# controller_board.net
KiCad netlist of a schematic drawn in EAGLE
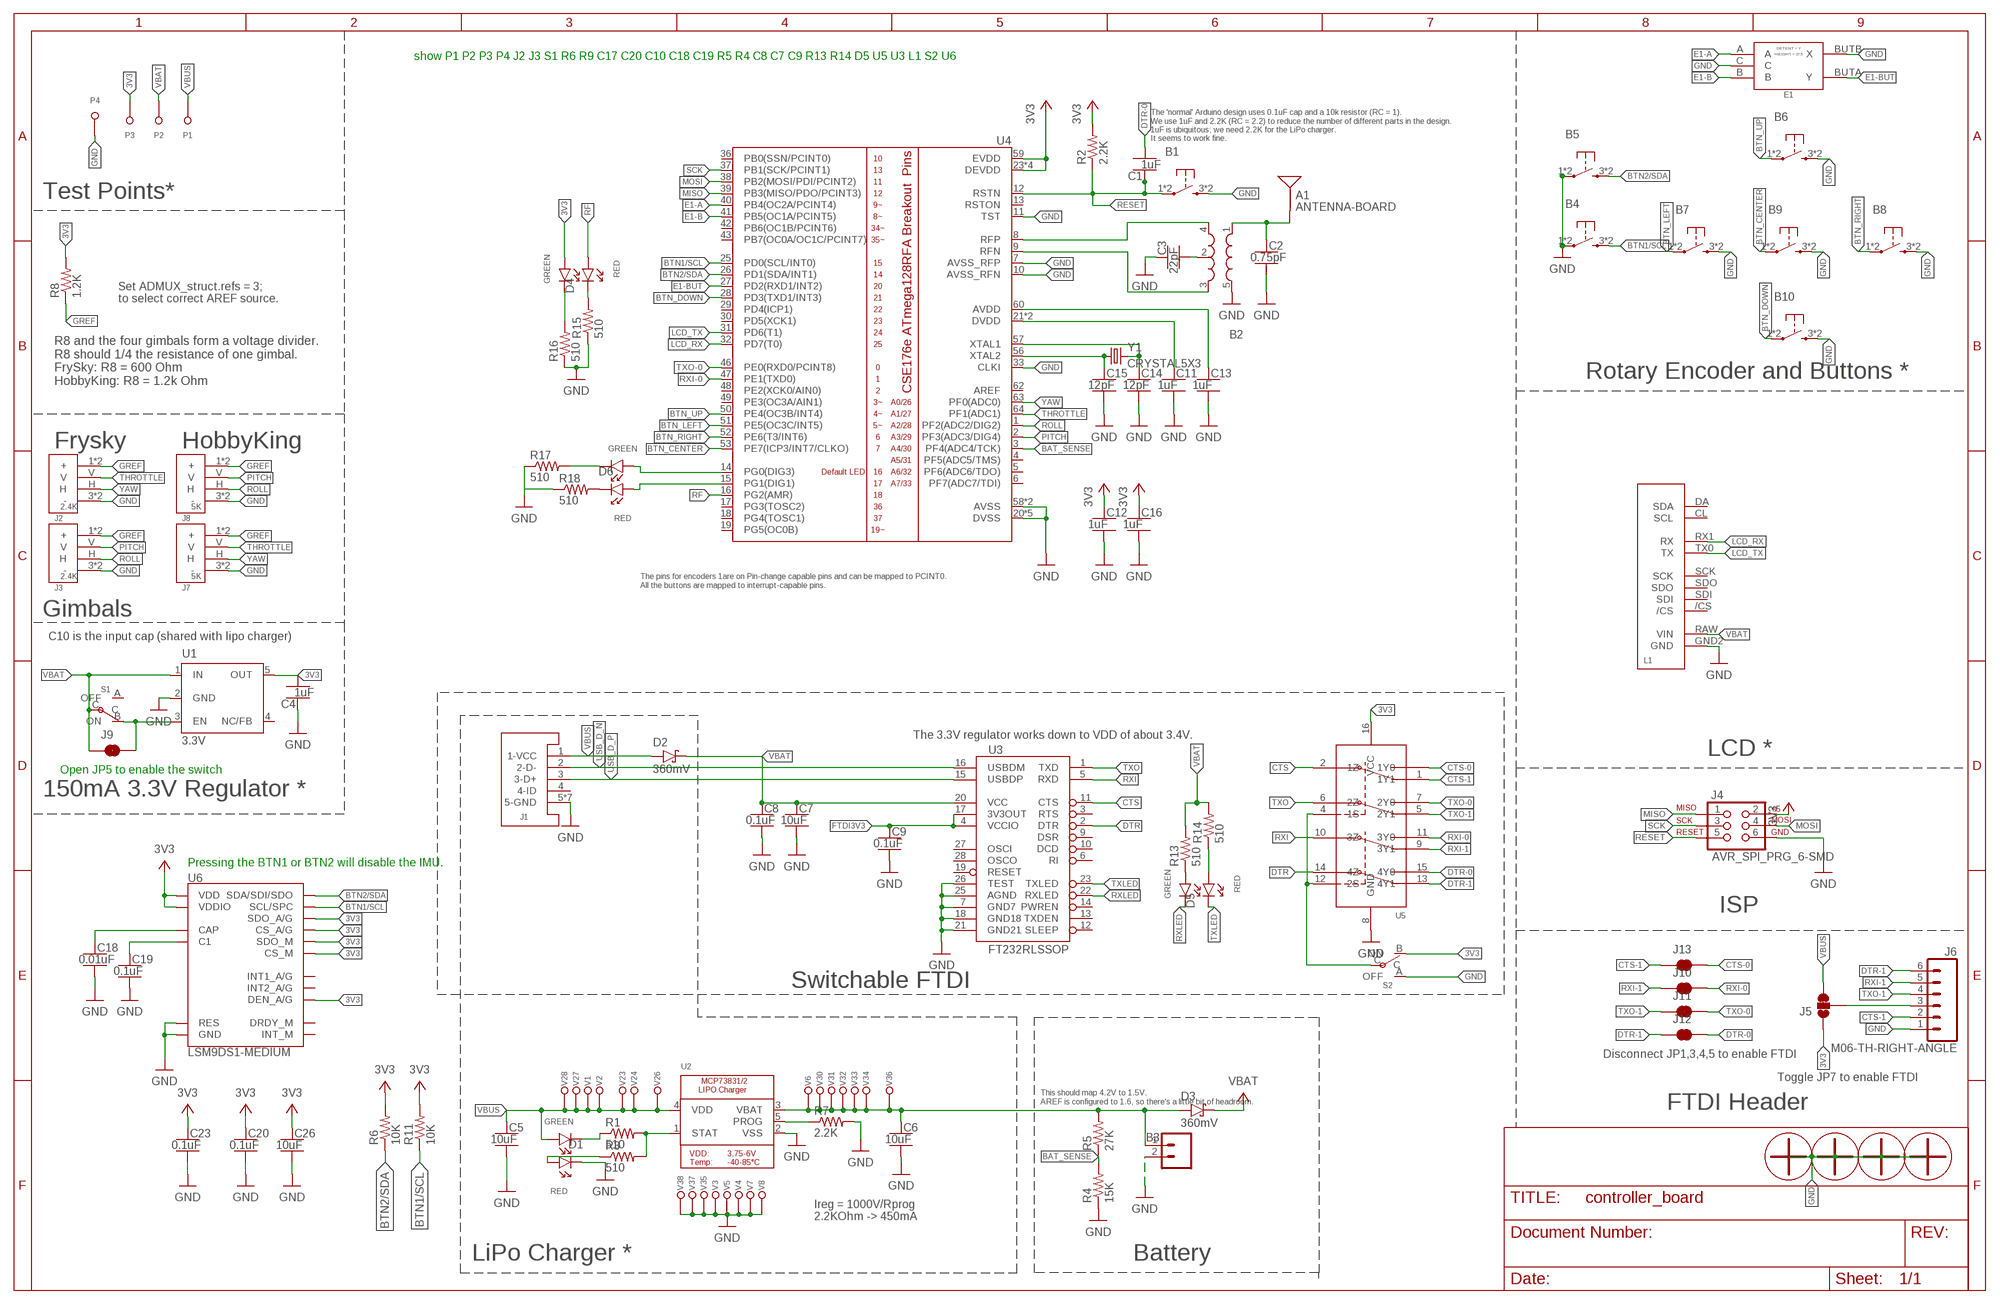
[diagram p0: schematic, sheet 1]

(export (version "E")
  (design (tool "Eeschema 10.0.6"))
  (components
    (comp (ref "A1")
      (value "ANTENNA-BOARD")
      (footprint "eagle-import:ANT_PCB_2.4GHZ_NRF8001_1.6MM_1OZ")
      (fields (field (name "CREATOR") "Swanson"))
      (libsource (lib "eagle-import") (part "ANTENNA-BOARD"))
    )
    (comp (ref "B1")
      (value "PUSHBUTTON_-4.5X4.5")
      (footprint "eagle-import:4.5MM_TACTILE_SWITCH_TL3305AF160QG")
      (fields (field (name "CREATOR") "Swanson"))
      (libsource (lib "eagle-import") (part "PUSHBUTTON_-4.5X4.5"))
    )
    (comp (ref "B2")
      (value "BALUN0805")
      (footprint "eagle-import:BALUN")
      (fields
        (field (name "MFR") "Wurth Electronics Inc")
        (field (name "MPN") "748421245")
        (field (name "CREATOR") "Swanson")
        (field (name "REVIEWER") "Swanson")
      )
      (libsource (lib "eagle-import") (part "BALUN0805"))
    )
    (comp (ref "B3")
      (value "HEADER-0.1IN-2POS-SCREW")
      (footprint "eagle-import:SCREW-TERMINAL-1X2-2.54MM")
      (fields (field (name "PIN1") "+") (field (name "PIN2") "-") (field (name "CREATOR") "Swanson"))
      (libsource (lib "eagle-import") (part "HEADER-0.1IN-2POS-SCREW"))
    )
    (comp (ref "B4")
      (value "PUSHBUTTON_-4.5X4.5")
      (footprint "eagle-import:4.5MM_TACTILE_SWITCH_TL3305AF160QG")
      (fields (field (name "CREATOR") "Swanson"))
      (libsource (lib "eagle-import") (part "PUSHBUTTON_-4.5X4.5"))
    )
    (comp (ref "B5")
      (value "PUSHBUTTON_-4.5X4.5")
      (footprint "eagle-import:4.5MM_TACTILE_SWITCH_TL3305AF160QG")
      (fields (field (name "CREATOR") "Swanson"))
      (libsource (lib "eagle-import") (part "PUSHBUTTON_-4.5X4.5"))
    )
    (comp (ref "B6")
      (value "PUSHBUTTON_-4.5X4.5")
      (footprint "eagle-import:4.5MM_TACTILE_SWITCH_TL3305AF160QG")
      (fields (field (name "CREATOR") "Swanson"))
      (libsource (lib "eagle-import") (part "PUSHBUTTON_-4.5X4.5"))
    )
    (comp (ref "B7")
      (value "PUSHBUTTON_-4.5X4.5")
      (footprint "eagle-import:4.5MM_TACTILE_SWITCH_TL3305AF160QG")
      (fields (field (name "CREATOR") "Swanson"))
      (libsource (lib "eagle-import") (part "PUSHBUTTON_-4.5X4.5"))
    )
    (comp (ref "B8")
      (value "PUSHBUTTON_-4.5X4.5")
      (footprint "eagle-import:4.5MM_TACTILE_SWITCH_TL3305AF160QG")
      (fields (field (name "CREATOR") "Swanson"))
      (libsource (lib "eagle-import") (part "PUSHBUTTON_-4.5X4.5"))
    )
    (comp (ref "B9")
      (value "PUSHBUTTON_-4.5X4.5")
      (footprint "eagle-import:4.5MM_TACTILE_SWITCH_TL3305AF160QG")
      (fields (field (name "CREATOR") "Swanson"))
      (libsource (lib "eagle-import") (part "PUSHBUTTON_-4.5X4.5"))
    )
    (comp (ref "B10")
      (value "PUSHBUTTON_-4.5X4.5")
      (footprint "eagle-import:4.5MM_TACTILE_SWITCH_TL3305AF160QG")
      (fields (field (name "CREATOR") "Swanson"))
      (libsource (lib "eagle-import") (part "PUSHBUTTON_-4.5X4.5"))
    )
    (comp (ref "C1")
      (value "1uF")
      (footprint "eagle-import:CAPC2012X140_HS")
      (fields
        (field (name "MFR") "Taiyo Yuden")
        (field (name "MPN") "TMK212B7105KG-T")
        (field (name "CREATOR") "Swanson")
        (field (name "REVIEWER") "Swanson")
      )
      (libsource (lib "eagle-import") (part "CAPACITOR-NP_SMD-2012-0805_CERAMIC-1UF"))
    )
    (comp (ref "C2")
      (value "0.75pF")
      (footprint "eagle-import:CAPC2012X140_HS")
      (fields
        (field (name "MFR") "Murata Electronics North America")
        (field (name "MPN") "GQM2195C2AR75CB01D")
        (field (name "CREATOR") "Swanson")
        (field (name "REVIEWER") "Swanson")
      )
      (libsource (lib "eagle-import") (part "CAPACITOR-NP_SMD-2012-0805_CERAMIC-0.75PF"))
    )
    (comp (ref "C3")
      (value "22pF")
      (footprint "eagle-import:CAPC2012X140_HS")
      (fields
        (field (name "MFR") "Murata Electronics North America")
        (field (name "MPN") "GRM21A5C2E220JW01D")
        (field (name "CREATOR") "Swanson")
        (field (name "REVIEWER") "Swanson")
      )
      (libsource (lib "eagle-import") (part "CAPACITOR-NP_SMD-2012-0805_CERAMIC-22PF"))
    )
    (comp (ref "C4")
      (value "1uF")
      (footprint "eagle-import:CAPC2012X140_HS")
      (fields
        (field (name "MFR") "Taiyo Yuden")
        (field (name "MPN") "TMK212B7105KG-T")
        (field (name "CREATOR") "Swanson")
        (field (name "REVIEWER") "Swanson")
      )
      (libsource (lib "eagle-import") (part "CAPACITOR-NP_SMD-2012-0805_CERAMIC-1UF"))
    )
    (comp (ref "C5")
      (value "10uF")
      (footprint "eagle-import:CAPC2012X140_HS")
      (fields (field (name "CREATOR") "Swanson") (field (name "REVIEWER") "Swanson"))
      (libsource (lib "eagle-import") (part "CAPACITOR-NP_SMD-2012-0805_CERAMIC-10UF"))
    )
    (comp (ref "C6")
      (value "10uF")
      (footprint "eagle-import:CAPC2012X140_HS")
      (fields (field (name "CREATOR") "Swanson") (field (name "REVIEWER") "Swanson"))
      (libsource (lib "eagle-import") (part "CAPACITOR-NP_SMD-2012-0805_CERAMIC-10UF"))
    )
    (comp (ref "C7")
      (value "10uF")
      (footprint "eagle-import:CAPC2012X140_HS")
      (fields (field (name "CREATOR") "Swanson") (field (name "REVIEWER") "Swanson"))
      (libsource (lib "eagle-import") (part "CAPACITOR-NP_SMD-2012-0805_CERAMIC-10UF"))
    )
    (comp (ref "C8")
      (value "0.1uF")
      (footprint "eagle-import:CAPC2012X140_HS")
      (fields
        (field (name "MFR") "TDK")
        (field (name "MPN") "C2012X7R2A104K125AA")
        (field (name "CREATOR") "Swanson")
        (field (name "REVIEWER") "Swanson")
      )
      (libsource (lib "eagle-import") (part "CAPACITOR-NP_SMD-2012-0805_CERAMIC-0.1UF"))
    )
    (comp (ref "C9")
      (value "0.1uF")
      (footprint "eagle-import:CAPC2012X140_HS")
      (fields
        (field (name "MFR") "TDK")
        (field (name "MPN") "C2012X7R2A104K125AA")
        (field (name "CREATOR") "Swanson")
        (field (name "REVIEWER") "Swanson")
      )
      (libsource (lib "eagle-import") (part "CAPACITOR-NP_SMD-2012-0805_CERAMIC-0.1UF"))
    )
    (comp (ref "C11")
      (value "1uF")
      (footprint "eagle-import:CAPC2012X140_HS")
      (fields
        (field (name "MFR") "Taiyo Yuden")
        (field (name "MPN") "TMK212B7105KG-T")
        (field (name "CREATOR") "Swanson")
        (field (name "REVIEWER") "Swanson")
      )
      (libsource (lib "eagle-import") (part "CAPACITOR-NP_SMD-2012-0805_CERAMIC-1UF"))
    )
    (comp (ref "C12")
      (value "1uF")
      (footprint "eagle-import:CAPC2012X140_HS")
      (fields
        (field (name "MFR") "Taiyo Yuden")
        (field (name "MPN") "TMK212B7105KG-T")
        (field (name "CREATOR") "Swanson")
        (field (name "REVIEWER") "Swanson")
      )
      (libsource (lib "eagle-import") (part "CAPACITOR-NP_SMD-2012-0805_CERAMIC-1UF"))
    )
    (comp (ref "C13")
      (value "1uF")
      (footprint "eagle-import:CAPC2012X140_HS")
      (fields
        (field (name "MFR") "Taiyo Yuden")
        (field (name "MPN") "TMK212B7105KG-T")
        (field (name "CREATOR") "Swanson")
        (field (name "REVIEWER") "Swanson")
      )
      (libsource (lib "eagle-import") (part "CAPACITOR-NP_SMD-2012-0805_CERAMIC-1UF"))
    )
    (comp (ref "C14")
      (value "12pF")
      (footprint "eagle-import:CAPC2012X140_HS")
      (fields
        (field (name "MFR") "Murata Electronics North America")
        (field (name "MPN") "GRM21A5C2E120JW01D")
        (field (name "CREATOR") "Swanson")
        (field (name "REVIEWER") "Swanson")
      )
      (libsource (lib "eagle-import") (part "CAPACITOR-NP_SMD-2012-0805_CERAMIC-12PF"))
    )
    (comp (ref "C15")
      (value "12pF")
      (footprint "eagle-import:CAPC2012X140_HS")
      (fields
        (field (name "MFR") "Murata Electronics North America")
        (field (name "MPN") "GRM21A5C2E120JW01D")
        (field (name "CREATOR") "Swanson")
        (field (name "REVIEWER") "Swanson")
      )
      (libsource (lib "eagle-import") (part "CAPACITOR-NP_SMD-2012-0805_CERAMIC-12PF"))
    )
    (comp (ref "C16")
      (value "1uF")
      (footprint "eagle-import:CAPC2012X140_HS")
      (fields
        (field (name "MFR") "Taiyo Yuden")
        (field (name "MPN") "TMK212B7105KG-T")
        (field (name "CREATOR") "Swanson")
        (field (name "REVIEWER") "Swanson")
      )
      (libsource (lib "eagle-import") (part "CAPACITOR-NP_SMD-2012-0805_CERAMIC-1UF"))
    )
    (comp (ref "C18")
      (value "0.01uF")
      (footprint "eagle-import:CAPC2012X140_HS")
      (fields
        (field (name "MFR") "Knowles Syfer")
        (field (name "MPN") "0805J0500104KJT")
        (field (name "CREATOR") "Swanson")
        (field (name "REVIEWER") "Swanson")
      )
      (libsource (lib "eagle-import") (part "CAPACITOR-NP_SMD-2012-0805_CERAMIC-0.01UF"))
    )
    (comp (ref "C19")
      (value "0.1uF")
      (footprint "eagle-import:CAPC2012X140_HS")
      (fields
        (field (name "MFR") "TDK")
        (field (name "MPN") "C2012X7R2A104K125AA")
        (field (name "CREATOR") "Swanson")
        (field (name "REVIEWER") "Swanson")
      )
      (libsource (lib "eagle-import") (part "CAPACITOR-NP_SMD-2012-0805_CERAMIC-0.1UF"))
    )
    (comp (ref "C20")
      (value "0.1uF")
      (footprint "eagle-import:CAPC2012X140_HS")
      (fields
        (field (name "MFR") "TDK")
        (field (name "MPN") "C2012X7R2A104K125AA")
        (field (name "CREATOR") "Swanson")
        (field (name "REVIEWER") "Swanson")
      )
      (libsource (lib "eagle-import") (part "CAPACITOR-NP_SMD-2012-0805_CERAMIC-0.1UF"))
    )
    (comp (ref "C23")
      (value "0.1uF")
      (footprint "eagle-import:CAPC2012X140_HS")
      (fields
        (field (name "MFR") "TDK")
        (field (name "MPN") "C2012X7R2A104K125AA")
        (field (name "CREATOR") "Swanson")
        (field (name "REVIEWER") "Swanson")
      )
      (libsource (lib "eagle-import") (part "CAPACITOR-NP_SMD-2012-0805_CERAMIC-0.1UF"))
    )
    (comp (ref "C26")
      (value "10uF")
      (footprint "eagle-import:CAPC2012X140_HS")
      (fields (field (name "CREATOR") "Swanson") (field (name "REVIEWER") "Swanson"))
      (libsource (lib "eagle-import") (part "CAPACITOR-NP_SMD-2012-0805_CERAMIC-10UF"))
    )
    (comp (ref "D1")
      (value "LED-2X-GREEN/RED")
      (footprint "eagle-import:LED-2X-LTST-C155")
      (fields
        (field (name "COLOR2") "RED")
        (field (name "COLOR1") "GREEN")
        (field (name "CREATOR") "Swanson")
      )
      (libsource (lib "eagle-import") (part "LED-2X-GREEN/RED"))
    )
    (comp (ref "D2")
      (value "360mV")
      (footprint "eagle-import:SOD3716X135_HS")
      (fields
        (field (name "MFR") "Toshiba Semiconductor and Storage")
        (field (name "MPN") "CRS08(TE85L,Q,M)")
        (field (name "CREATOR") "Swanson")
        (field (name "REVIEWER") "Swanson")
      )
      (libsource (lib "eagle-import") (part "DIODE-SCHOTTKY_SMD-SOD123-360MV"))
    )
    (comp (ref "D3")
      (value "360mV")
      (footprint "eagle-import:SOD3716X135_HS")
      (fields
        (field (name "MFR") "Toshiba Semiconductor and Storage")
        (field (name "MPN") "CRS08(TE85L,Q,M)")
        (field (name "CREATOR") "Swanson")
        (field (name "REVIEWER") "Swanson")
      )
      (libsource (lib "eagle-import") (part "DIODE-SCHOTTKY_SMD-SOD123-360MV"))
    )
    (comp (ref "D4")
      (value "LED-2X-GREEN/RED")
      (footprint "eagle-import:LED-2X-LTST-C155")
      (fields
        (field (name "COLOR2") "RED")
        (field (name "COLOR1") "GREEN")
        (field (name "CREATOR") "Swanson")
      )
      (libsource (lib "eagle-import") (part "LED-2X-GREEN/RED"))
    )
    (comp (ref "D5")
      (value "LED-2X-GREEN/RED")
      (footprint "eagle-import:LED-2X-LTST-C155")
      (fields
        (field (name "COLOR2") "RED")
        (field (name "COLOR1") "GREEN")
        (field (name "CREATOR") "Swanson")
      )
      (libsource (lib "eagle-import") (part "LED-2X-GREEN/RED"))
    )
    (comp (ref "D6")
      (value "LED-2X-GREEN/RED")
      (footprint "eagle-import:LED-2X-LTST-C155")
      (fields
        (field (name "COLOR2") "RED")
        (field (name "COLOR1") "GREEN")
        (field (name "CREATOR") "Swanson")
      )
      (libsource (lib "eagle-import") (part "LED-2X-GREEN/RED"))
    )
    (comp (ref "E1")
      (value "ROTARY-ENCODER-W/BUTTON-BOURNS-PEC12R-4217F")
      (footprint "eagle-import:BOURNS-PEC12R")
      (fields (field (name "DETENT") "Y") (field (name "HEIGHT") "17.5") (field (name "CREATOR") "Swanson"))
      (libsource (lib "eagle-import") (part "ROTARY-ENCODER-W/BUTTON-BOURNS-PEC12R-4217F"))
    )
    (comp (ref "H1")
      (value "MOUNTING-HOLE-2-56-GROUNDED")
      (footprint "eagle-import:2-56-MOUNTING-HOLE")
      (fields (field (name "CREATOR") "Swanson"))
      (libsource (lib "eagle-import") (part "MOUNTING-HOLE-2-56-GROUNDED"))
    )
    (comp (ref "H2")
      (value "MOUNTING-HOLE-2-56-GROUNDED")
      (footprint "eagle-import:2-56-MOUNTING-HOLE")
      (fields (field (name "CREATOR") "Swanson"))
      (libsource (lib "eagle-import") (part "MOUNTING-HOLE-2-56-GROUNDED"))
    )
    (comp (ref "H3")
      (value "MOUNTING-HOLE-2-56-GROUNDED")
      (footprint "eagle-import:2-56-MOUNTING-HOLE")
      (fields (field (name "CREATOR") "Swanson"))
      (libsource (lib "eagle-import") (part "MOUNTING-HOLE-2-56-GROUNDED"))
    )
    (comp (ref "H4")
      (value "MOUNTING-HOLE-2-56-GROUNDED")
      (footprint "eagle-import:2-56-MOUNTING-HOLE")
      (fields (field (name "CREATOR") "Swanson"))
      (libsource (lib "eagle-import") (part "MOUNTING-HOLE-2-56-GROUNDED"))
    )
    (comp (ref "J1")
      (value "USB-MICROA-AMPHENOL-10118192-0001LF")
      (footprint "eagle-import:USB-MICROA-10118192-0001LF")
      (fields (field (name "CREATOR") "Swanson"))
      (libsource (lib "eagle-import") (part "USB-MICROA-AMPHENOL-10118192-0001LF"))
    )
    (comp (ref "J2")
      (value "2.4K")
      (footprint "eagle-import:JST-13-PTH")
      (fields (field (name "CREATOR") "Swanson"))
      (libsource (lib "eagle-import") (part "FRSKY-GIMBAL-FRYSKY"))
    )
    (comp (ref "J3")
      (value "2.4K")
      (footprint "eagle-import:JST-13-PTH")
      (fields (field (name "SPICEPREFIX") "E") (field (name "CREATOR") "Swanson"))
      (libsource (lib "eagle-import") (part "FRSKY-GIMBAL-FRYSKY"))
    )
    (comp (ref "J4")
      (value "AVR_SPI_PRG_6-SMD")
      (footprint "eagle-import:2X3-SMD")
      (fields (field (name "CREATOR") "Swanson"))
      (libsource (lib "eagle-import") (part "AVR_SPI_PRG_6-SMD"))
    )
    (comp (ref "J5")
      (value "JUMPER-SMT_3_1-NC_TRACE_NO-SILK")
      (footprint "eagle-import:SMT-JUMPER_3_1-NC_TRACE_NO-SILK")
      (fields (field (name "CREATOR") "Sparkfun"))
      (libsource (lib "eagle-import") (part "JUMPER-SMT_3_1-NC_TRACE_NO-SILK"))
    )
    (comp (ref "J6")
      (value "M06-TH-RIGHT-ANGLE")
      (footprint "eagle-import:1X06-SIP-RIGHT-ANGLE")
      (fields (field (name "CREATOR") "Swanson"))
      (libsource (lib "eagle-import") (part "M06-TH-RIGHT-ANGLE"))
    )
    (comp (ref "J7")
      (value "5K")
      (footprint "eagle-import:2X-GIMBAL-SERVO")
      (fields (field (name "CREATOR") "Swanson"))
      (libsource (lib "eagle-import") (part "FRSKY-GIMBAL-2X-SERVO"))
    )
    (comp (ref "J8")
      (value "5K")
      (footprint "eagle-import:2X-GIMBAL-SERVO")
      (fields (field (name "CREATOR") "Swanson"))
      (libsource (lib "eagle-import") (part "FRSKY-GIMBAL-2X-SERVO"))
    )
    (comp (ref "J9")
      (value "JUMPER-SMT_2_NC_TRACE_NO-SILK")
      (footprint "eagle-import:SMT-JUMPER_2_NC_TRACE_NO-SILK")
      (fields (field (name "CREATOR") "Sparkfun"))
      (libsource (lib "eagle-import") (part "JUMPER-SMT_2_NC_TRACE_NO-SILK"))
    )
    (comp (ref "J10")
      (value "JUMPER-SMT_2_NC_TRACE_NO-SILK")
      (footprint "eagle-import:SMT-JUMPER_2_NC_TRACE_NO-SILK")
      (fields (field (name "CREATOR") "Sparkfun"))
      (libsource (lib "eagle-import") (part "JUMPER-SMT_2_NC_TRACE_NO-SILK"))
    )
    (comp (ref "J11")
      (value "JUMPER-SMT_2_NC_TRACE_NO-SILK")
      (footprint "eagle-import:SMT-JUMPER_2_NC_TRACE_NO-SILK")
      (fields (field (name "CREATOR") "Sparkfun"))
      (libsource (lib "eagle-import") (part "JUMPER-SMT_2_NC_TRACE_NO-SILK"))
    )
    (comp (ref "J12")
      (value "JUMPER-SMT_2_NC_TRACE_NO-SILK")
      (footprint "eagle-import:SMT-JUMPER_2_NC_TRACE_NO-SILK")
      (fields (field (name "CREATOR") "Sparkfun"))
      (libsource (lib "eagle-import") (part "JUMPER-SMT_2_NC_TRACE_NO-SILK"))
    )
    (comp (ref "J13")
      (value "JUMPER-SMT_2_NC_TRACE_NO-SILK")
      (footprint "eagle-import:SMT-JUMPER_2_NC_TRACE_NO-SILK")
      (fields (field (name "CREATOR") "Sparkfun"))
      (libsource (lib "eagle-import") (part "JUMPER-SMT_2_NC_TRACE_NO-SILK"))
    )
    (comp (ref "L1")
      (value "SPARKFUN_SERLCD_SERIAL_REDUCED")
      (footprint "eagle-import:SPARKFUN_SERLCD_16X2_REDUCED")
      (fields (field (name "CREATOR") "Swanson"))
      (libsource (lib "eagle-import") (part "SPARKFUN_SERLCD_SERIAL_REDUCED"))
    )
    (comp (ref "P1")
      (value "TEST-POINT")
      (footprint "eagle-import:TEST-POINT-KEYSTONE-5000")
      (fields (field (name "CREATOR") "Swanson"))
      (libsource (lib "eagle-import") (part "TEST-POINT"))
    )
    (comp (ref "P2")
      (value "TEST-POINT")
      (footprint "eagle-import:TEST-POINT-KEYSTONE-5000")
      (fields (field (name "CREATOR") "Swanson"))
      (libsource (lib "eagle-import") (part "TEST-POINT"))
    )
    (comp (ref "P3")
      (value "TEST-POINT")
      (footprint "eagle-import:TEST-POINT-KEYSTONE-5000")
      (fields (field (name "CREATOR") "Swanson"))
      (libsource (lib "eagle-import") (part "TEST-POINT"))
    )
    (comp (ref "P4")
      (value "TEST-POINT")
      (footprint "eagle-import:TEST-POINT-KEYSTONE-5000")
      (fields (field (name "CREATOR") "Swanson"))
      (libsource (lib "eagle-import") (part "TEST-POINT"))
    )
    (comp (ref "R1")
      (value "510")
      (footprint "eagle-import:RESC2012X60_HS")
      (fields (field (name "CREATOR") "SWANSON"))
      (libsource (lib "eagle-import") (part "RESISTOR_SMD-2012-0805-510"))
    )
    (comp (ref "R2")
      (value "2.2K")
      (footprint "eagle-import:RESC2012X60_HS")
      (fields (field (name "CREATOR") "SWANSON"))
      (libsource (lib "eagle-import") (part "RESISTOR_SMD-2012-0805-2.2K"))
    )
    (comp (ref "R3")
      (value "510")
      (footprint "eagle-import:RESC2012X60_HS")
      (fields (field (name "CREATOR") "SWANSON"))
      (libsource (lib "eagle-import") (part "RESISTOR_SMD-2012-0805-510"))
    )
    (comp (ref "R4")
      (value "15K")
      (footprint "eagle-import:RESC2012X60_HS")
      (fields (field (name "CREATOR") "SWANSON"))
      (libsource (lib "eagle-import") (part "RESISTOR_SMD-2012-0805-15K"))
    )
    (comp (ref "R5")
      (value "27K")
      (footprint "eagle-import:RESC2012X60_HS")
      (fields (field (name "CREATOR") "Swanson"))
      (libsource (lib "eagle-import") (part "RESISTOR_SMD-2012-0805-27K"))
    )
    (comp (ref "R6")
      (value "10K")
      (footprint "eagle-import:RESC2012X60_HS")
      (fields
        (field (name "MFR") "Yageo")
        (field (name "MPN") "RC0805JR-0710KL")
        (field (name "CREATOR") "Swanson")
        (field (name "REVIEWER") "Swanson")
      )
      (libsource (lib "eagle-import") (part "RESISTOR_SMD-2012-0805-10K"))
    )
    (comp (ref "R7")
      (value "2.2K")
      (footprint "eagle-import:RESC2012X60_HS")
      (fields (field (name "CREATOR") "SWANSON"))
      (libsource (lib "eagle-import") (part "RESISTOR_SMD-2012-0805-2.2K"))
    )
    (comp (ref "R8")
      (value "1.2K")
      (footprint "eagle-import:RESC2012X60_HS")
      (fields (field (name "CREATOR") "Swanson"))
      (libsource (lib "eagle-import") (part "RESISTOR_SMD-2012-0805-1.2K"))
    )
    (comp (ref "R11")
      (value "10K")
      (footprint "eagle-import:RESC2012X60_HS")
      (fields
        (field (name "MFR") "Yageo")
        (field (name "MPN") "RC0805JR-0710KL")
        (field (name "CREATOR") "Swanson")
        (field (name "REVIEWER") "Swanson")
      )
      (libsource (lib "eagle-import") (part "RESISTOR_SMD-2012-0805-10K"))
    )
    (comp (ref "R13")
      (value "510")
      (footprint "eagle-import:RESC2012X60_HS")
      (fields (field (name "CREATOR") "SWANSON"))
      (libsource (lib "eagle-import") (part "RESISTOR_SMD-2012-0805-510"))
    )
    (comp (ref "R14")
      (value "510")
      (footprint "eagle-import:RESC2012X60_HS")
      (fields (field (name "CREATOR") "SWANSON"))
      (libsource (lib "eagle-import") (part "RESISTOR_SMD-2012-0805-510"))
    )
    (comp (ref "R15")
      (value "510")
      (footprint "eagle-import:RESC2012X60_HS")
      (fields (field (name "CREATOR") "SWANSON"))
      (libsource (lib "eagle-import") (part "RESISTOR_SMD-2012-0805-510"))
    )
    (comp (ref "R16")
      (value "510")
      (footprint "eagle-import:RESC2012X60_HS")
      (fields (field (name "CREATOR") "SWANSON"))
      (libsource (lib "eagle-import") (part "RESISTOR_SMD-2012-0805-510"))
    )
    (comp (ref "R17")
      (value "510")
      (footprint "eagle-import:RESC2012X60_HS")
      (fields (field (name "CREATOR") "SWANSON"))
      (libsource (lib "eagle-import") (part "RESISTOR_SMD-2012-0805-510"))
    )
    (comp (ref "R18")
      (value "510")
      (footprint "eagle-import:RESC2012X60_HS")
      (fields (field (name "CREATOR") "SWANSON"))
      (libsource (lib "eagle-import") (part "RESISTOR_SMD-2012-0805-510"))
    )
    (comp (ref "S1")
      (value "POWER-SWITCH-MFS201N-9-ZJS102011SAQN")
      (footprint "eagle-import:JS102011SAQN")
      (fields (field (name "CREATOR") "Swanson"))
      (libsource (lib "eagle-import") (part "POWER-SWITCH-MFS201N-9-ZJS102011SAQN"))
    )
    (comp (ref "S2")
      (value "POWER-SWITCH-MFS201N-9-ZJS102011SAQN")
      (footprint "eagle-import:JS102011SAQN")
      (fields (field (name "CREATOR") "Swanson"))
      (libsource (lib "eagle-import") (part "POWER-SWITCH-MFS201N-9-ZJS102011SAQN"))
    )
    (comp (ref "U1")
      (value "3.3V")
      (footprint "eagle-import:SOT23-DBV")
      (fields (field (name "CREATOR") "Swanson"))
      (libsource (lib "eagle-import") (part "TPS73633-DBVT3V3"))
    )
    (comp (ref "U2")
      (value "MCP73831T-2ACI/OT")
      (footprint "eagle-import:SOT23-5")
      (fields (field (name "CREATOR") "Adafruit"))
      (libsource (lib "eagle-import") (part "MCP73831/2"))
    )
    (comp (ref "U3")
      (value "FT232RLSSOP")
      (footprint "eagle-import:SSOP28DB")
      (fields (field (name "CREATOR") "Swanson"))
      (libsource (lib "eagle-import") (part "FT232RLSSOP"))
    )
    (comp (ref "U4")
      (value "ATMEGA128RFA1")
      (footprint "eagle-import:QFN-64")
      (fields
        (field (name "MFR") "Atmel")
        (field (name "MPN") "ATMEGA128RFA1-ZUR00")
        (field (name "CREATOR") "Swanson")
        (field (name "REVIEWER") "Swanson")
      )
      (libsource (lib "eagle-import") (part "ATMEGA128RFA1"))
    )
    (comp (ref "U5")
      (value "DPDT-X2")
      (footprint "eagle-import:SOP65P640X110-16")
      (fields (field (name "CREATOR") "Swanson"))
      (libsource (lib "eagle-import") (part "DPDT-X2"))
    )
    (comp (ref "U6")
      (value "LSM9DS1-MEDIUM")
      (footprint "eagle-import:NEW_IMU_MEDIUM")
      (fields (field (name "CREATOR") "PBROWN"))
      (libsource (lib "eagle-import") (part "LSM9DS1-MEDIUM"))
    )
    (comp (ref "V1")
      (value "LOCKED-VIA-0.2")
      (footprint "eagle-import:VIA-0.2MM")
      (fields (field (name "CREATOR") "Swanson"))
      (libsource (lib "eagle-import") (part "LOCKED-VIA-0.2"))
    )
    (comp (ref "V2")
      (value "LOCKED-VIA-0.2")
      (footprint "eagle-import:VIA-0.2MM")
      (fields (field (name "CREATOR") "Swanson"))
      (libsource (lib "eagle-import") (part "LOCKED-VIA-0.2"))
    )
    (comp (ref "V3")
      (value "LOCKED-VIA-0.2")
      (footprint "eagle-import:VIA-0.2MM")
      (fields (field (name "CREATOR") "Swanson"))
      (libsource (lib "eagle-import") (part "LOCKED-VIA-0.2"))
    )
    (comp (ref "V4")
      (value "LOCKED-VIA-0.2")
      (footprint "eagle-import:VIA-0.2MM")
      (fields (field (name "CREATOR") "Swanson"))
      (libsource (lib "eagle-import") (part "LOCKED-VIA-0.2"))
    )
    (comp (ref "V5")
      (value "LOCKED-VIA-0.2")
      (footprint "eagle-import:VIA-0.2MM")
      (fields (field (name "CREATOR") "Swanson"))
      (libsource (lib "eagle-import") (part "LOCKED-VIA-0.2"))
    )
    (comp (ref "V6")
      (value "LOCKED-VIA-0.2")
      (footprint "eagle-import:VIA-0.2MM")
      (fields (field (name "CREATOR") "Swanson"))
      (libsource (lib "eagle-import") (part "LOCKED-VIA-0.2"))
    )
    (comp (ref "V7")
      (value "LOCKED-VIA-0.2")
      (footprint "eagle-import:VIA-0.2MM")
      (fields (field (name "CREATOR") "Swanson"))
      (libsource (lib "eagle-import") (part "LOCKED-VIA-0.2"))
    )
    (comp (ref "V8")
      (value "LOCKED-VIA-0.2")
      (footprint "eagle-import:VIA-0.2MM")
      (fields (field (name "CREATOR") "Swanson"))
      (libsource (lib "eagle-import") (part "LOCKED-VIA-0.2"))
    )
    (comp (ref "V23")
      (value "LOCKED-VIA-0.2")
      (footprint "eagle-import:VIA-0.2MM")
      (fields (field (name "CREATOR") "Swanson"))
      (libsource (lib "eagle-import") (part "LOCKED-VIA-0.2"))
    )
    (comp (ref "V24")
      (value "LOCKED-VIA-0.2")
      (footprint "eagle-import:VIA-0.2MM")
      (fields (field (name "CREATOR") "Swanson"))
      (libsource (lib "eagle-import") (part "LOCKED-VIA-0.2"))
    )
    (comp (ref "V26")
      (value "LOCKED-VIA-0.2")
      (footprint "eagle-import:VIA-0.2MM")
      (fields (field (name "CREATOR") "Swanson"))
      (libsource (lib "eagle-import") (part "LOCKED-VIA-0.2"))
    )
    (comp (ref "V27")
      (value "LOCKED-VIA-0.2")
      (footprint "eagle-import:VIA-0.2MM")
      (fields (field (name "CREATOR") "Swanson"))
      (libsource (lib "eagle-import") (part "LOCKED-VIA-0.2"))
    )
    (comp (ref "V28")
      (value "LOCKED-VIA-0.2")
      (footprint "eagle-import:VIA-0.2MM")
      (fields (field (name "CREATOR") "Swanson"))
      (libsource (lib "eagle-import") (part "LOCKED-VIA-0.2"))
    )
    (comp (ref "V30")
      (value "LOCKED-VIA-0.2")
      (footprint "eagle-import:VIA-0.2MM")
      (fields (field (name "CREATOR") "Swanson"))
      (libsource (lib "eagle-import") (part "LOCKED-VIA-0.2"))
    )
    (comp (ref "V31")
      (value "LOCKED-VIA-0.2")
      (footprint "eagle-import:VIA-0.2MM")
      (fields (field (name "CREATOR") "Swanson"))
      (libsource (lib "eagle-import") (part "LOCKED-VIA-0.2"))
    )
    (comp (ref "V32")
      (value "LOCKED-VIA-0.2")
      (footprint "eagle-import:VIA-0.2MM")
      (fields (field (name "CREATOR") "Swanson"))
      (libsource (lib "eagle-import") (part "LOCKED-VIA-0.2"))
    )
    (comp (ref "V33")
      (value "LOCKED-VIA-0.2")
      (footprint "eagle-import:VIA-0.2MM")
      (fields (field (name "CREATOR") "Swanson"))
      (libsource (lib "eagle-import") (part "LOCKED-VIA-0.2"))
    )
    (comp (ref "V34")
      (value "LOCKED-VIA-0.2")
      (footprint "eagle-import:VIA-0.2MM")
      (fields (field (name "CREATOR") "Swanson"))
      (libsource (lib "eagle-import") (part "LOCKED-VIA-0.2"))
    )
    (comp (ref "V35")
      (value "LOCKED-VIA-0.2")
      (footprint "eagle-import:VIA-0.2MM")
      (fields (field (name "CREATOR") "Swanson"))
      (libsource (lib "eagle-import") (part "LOCKED-VIA-0.2"))
    )
    (comp (ref "V36")
      (value "LOCKED-VIA-0.2")
      (footprint "eagle-import:VIA-0.2MM")
      (fields (field (name "CREATOR") "Swanson"))
      (libsource (lib "eagle-import") (part "LOCKED-VIA-0.2"))
    )
    (comp (ref "V37")
      (value "LOCKED-VIA-0.2")
      (footprint "eagle-import:VIA-0.2MM")
      (fields (field (name "CREATOR") "Swanson"))
      (libsource (lib "eagle-import") (part "LOCKED-VIA-0.2"))
    )
    (comp (ref "V38")
      (value "LOCKED-VIA-0.2")
      (footprint "eagle-import:VIA-0.2MM")
      (fields (field (name "CREATOR") "Swanson"))
      (libsource (lib "eagle-import") (part "LOCKED-VIA-0.2"))
    )
    (comp (ref "Y1")
      (value "CRYSTAL5X3")
      (footprint "eagle-import:CRYSTAL-SMD-5X3")
      (fields
        (field (name "MFR") "Abracon LLC")
        (field (name "MPN") "ABM3B-16.000MHZ-B2-T")
        (field (name "CREATOR") "Swanson")
        (field (name "REVIEWER") "Swanson")
      )
      (libsource (lib "eagle-import") (part "CRYSTAL5X3"))
    )
  )
  (nets
    (net (code "1") (name "3V3") (class "Default")
      (node (ref "C12") (pin "1") (pinfunction "1_1") (pintype "passive"))
      (node (ref "C16") (pin "1") (pinfunction "1_1") (pintype "passive"))
      (node (ref "C20") (pin "1") (pinfunction "1_1") (pintype "passive"))
      (node (ref "C23") (pin "1") (pinfunction "1_1") (pintype "passive"))
      (node (ref "C26") (pin "1") (pinfunction "1_1") (pintype "passive"))
      (node (ref "C4") (pin "2") (pinfunction "2_2") (pintype "passive"))
      (node (ref "D4") (pin "A2") (pinfunction "A2_A2") (pintype "passive"))
      (node (ref "J4") (pin "2") (pinfunction "2_2") (pintype "passive"))
      (node (ref "J5") (pin "1") (pinfunction "1_1") (pintype "passive"))
      (node (ref "P3") (pin "T") (pinfunction "T_T") (pintype "bidirectional"))
      (node (ref "R11") (pin "2") (pinfunction "2_2") (pintype "passive"))
      (node (ref "R2") (pin "2") (pinfunction "2_2") (pintype "passive"))
      (node (ref "R6") (pin "2") (pinfunction "2_2") (pintype "passive"))
      (node (ref "R8") (pin "2") (pinfunction "2_2") (pintype "passive"))
      (node (ref "S2") (pin "B") (pinfunction "ON_B") (pintype "bidirectional"))
      (node (ref "U1") (pin "5") (pinfunction "OUT_5") (pintype "passive"))
      (node (ref "U4") (pin "23") (pinfunction "DEVDD_23") (pintype "bidirectional"))
      (node (ref "U4") (pin "34") (pinfunction "DEVDD_34") (pintype "bidirectional"))
      (node (ref "U4") (pin "44") (pinfunction "DEVDD_44") (pintype "bidirectional"))
      (node (ref "U4") (pin "54") (pinfunction "DEVDD_54") (pintype "bidirectional"))
      (node (ref "U4") (pin "59") (pinfunction "EVDD_59") (pintype "bidirectional"))
      (node (ref "U5") (pin "16") (pinfunction "VCC_16") (pintype "bidirectional"))
      (node (ref "U6") (pin "CS_A/G") (pinfunction "CS_A/G_CS_A/G") (pintype "bidirectional"))
      (node (ref "U6") (pin "CS_M") (pinfunction "CS_M_CS_M") (pintype "bidirectional"))
      (node (ref "U6") (pin "DEN_A/G") (pinfunction "DEN_A/G_DEN_A/G") (pintype "bidirectional"))
      (node (ref "U6") (pin "SDO_A/G") (pinfunction "SDO_A/G_SDO_A/G") (pintype "bidirectional"))
      (node (ref "U6") (pin "SDO_M") (pinfunction "SDO_M_SDO_M") (pintype "bidirectional"))
      (node (ref "U6") (pin "VDD1") (pinfunction "VDD_VDD1") (pintype "bidirectional"))
      (node (ref "U6") (pin "VDD2") (pinfunction "VDD_VDD2") (pintype "bidirectional"))
      (node (ref "U6") (pin "VDDIO") (pinfunction "VDDIO_VDDIO") (pintype "bidirectional"))
      (node (ref "U6") (pin "VDDIO2") (pinfunction "VDDIO_VDDIO2") (pintype "bidirectional"))
    )
    (net (code "2") (name "BAT_SENSE") (class "Default")
      (node (ref "R4") (pin "2") (pinfunction "2_2") (pintype "passive"))
      (node (ref "R5") (pin "1") (pinfunction "1_1") (pintype "passive"))
      (node (ref "U4") (pin "3") (pinfunction "PF4(ADC4/TCK)_3") (pintype "bidirectional"))
    )
    (net (code "3") (name "BTN1{slash}SCL") (class "Default")
      (node (ref "B4") (pin "3") (pinfunction "2_3") (pintype "passive"))
      (node (ref "B4") (pin "4") (pinfunction "2_4") (pintype "passive"))
      (node (ref "R11") (pin "1") (pinfunction "1_1") (pintype "passive"))
      (node (ref "U4") (pin "25") (pinfunction "PD0(SCL/INT0)_25") (pintype "bidirectional"))
      (node (ref "U6") (pin "SCL/SPC") (pinfunction "SCL/SPC_SCL/SPC") (pintype "bidirectional"))
    )
    (net (code "4") (name "BTN2{slash}SDA") (class "Default")
      (node (ref "B5") (pin "3") (pinfunction "2_3") (pintype "passive"))
      (node (ref "B5") (pin "4") (pinfunction "2_4") (pintype "passive"))
      (node (ref "R6") (pin "1") (pinfunction "1_1") (pintype "passive"))
      (node (ref "U4") (pin "26") (pinfunction "PD1(SDA/INT1)_26") (pintype "bidirectional"))
      (node (ref "U6") (pin "SDA/SDI/SDO") (pinfunction "SDA/SDI/SDO_SDA/SDI/SDO") (pintype "bidirectional"))
    )
    (net (code "5") (name "BTN_CENTER") (class "Default")
      (node (ref "B9") (pin "1") (pinfunction "1_1") (pintype "passive"))
      (node (ref "B9") (pin "2") (pinfunction "1_2") (pintype "passive"))
      (node (ref "U4") (pin "53") (pinfunction "PE7(ICP3/INT7/CLKO)_53") (pintype "bidirectional"))
    )
    (net (code "6") (name "BTN_DOWN") (class "Default")
      (node (ref "B10") (pin "1") (pinfunction "1_1") (pintype "passive"))
      (node (ref "B10") (pin "2") (pinfunction "1_2") (pintype "passive"))
      (node (ref "U4") (pin "28") (pinfunction "PD3(TXD1/INT3)_28") (pintype "bidirectional"))
    )
    (net (code "7") (name "BTN_LEFT") (class "Default")
      (node (ref "B7") (pin "1") (pinfunction "1_1") (pintype "passive"))
      (node (ref "B7") (pin "2") (pinfunction "1_2") (pintype "passive"))
      (node (ref "U4") (pin "51") (pinfunction "PE5(OC3C/INT5)_51") (pintype "bidirectional"))
    )
    (net (code "8") (name "BTN_RIGHT") (class "Default")
      (node (ref "B8") (pin "1") (pinfunction "1_1") (pintype "passive"))
      (node (ref "B8") (pin "2") (pinfunction "1_2") (pintype "passive"))
      (node (ref "U4") (pin "52") (pinfunction "PE6(T3/INT6)_52") (pintype "bidirectional"))
    )
    (net (code "9") (name "BTN_UP") (class "Default")
      (node (ref "B6") (pin "1") (pinfunction "1_1") (pintype "passive"))
      (node (ref "B6") (pin "2") (pinfunction "1_2") (pintype "passive"))
      (node (ref "U4") (pin "50") (pinfunction "PE4(OC3B/INT4)_50") (pintype "bidirectional"))
    )
    (net (code "10") (name "CTS") (class "Default")
      (node (ref "U3") (pin "11") (pinfunction "CTS_11") (pintype "input"))
      (node (ref "U5") (pin "2") (pinfunction "1Z_2") (pintype "bidirectional"))
    )
    (net (code "11") (name "CTS-0") (class "Default")
      (node (ref "J13") (pin "2") (pinfunction "2_2") (pintype "passive"))
      (node (ref "U5") (pin "3") (pinfunction "1Y0_3") (pintype "bidirectional"))
    )
    (net (code "12") (name "CTS-1") (class "Default")
      (node (ref "J13") (pin "1") (pinfunction "1_1") (pintype "passive"))
      (node (ref "J6") (pin "2") (pinfunction "2_2") (pintype "passive"))
      (node (ref "U5") (pin "1") (pinfunction "1Y1_1") (pintype "bidirectional"))
    )
    (net (code "13") (name "DTR") (class "Default")
      (node (ref "U3") (pin "2") (pinfunction "DTR_2") (pintype "output"))
      (node (ref "U5") (pin "14") (pinfunction "4Z_14") (pintype "bidirectional"))
    )
    (net (code "14") (name "DTR-0") (class "Default")
      (node (ref "C1") (pin "2") (pinfunction "2_2") (pintype "passive"))
      (node (ref "J12") (pin "2") (pinfunction "2_2") (pintype "passive"))
      (node (ref "U5") (pin "15") (pinfunction "4Y0_15") (pintype "bidirectional"))
    )
    (net (code "15") (name "DTR-1") (class "Default")
      (node (ref "J12") (pin "1") (pinfunction "1_1") (pintype "passive"))
      (node (ref "J6") (pin "6") (pinfunction "6_6") (pintype "passive"))
      (node (ref "U5") (pin "13") (pinfunction "4Y1_13") (pintype "bidirectional"))
    )
    (net (code "16") (name "E1-A") (class "Default")
      (node (ref "E1") (pin "A") (pinfunction "A_A") (pintype "bidirectional"))
      (node (ref "U4") (pin "40") (pinfunction "PB4(OC2A/PCINT4)_40") (pintype "bidirectional"))
    )
    (net (code "17") (name "E1-B") (class "Default")
      (node (ref "E1") (pin "B") (pinfunction "B_B") (pintype "bidirectional"))
      (node (ref "U4") (pin "41") (pinfunction "PB5(OC1A/PCINT5)_41") (pintype "bidirectional"))
    )
    (net (code "18") (name "E1-BUT") (class "Default")
      (node (ref "E1") (pin "BUTA") (pinfunction "Y_BUTA") (pintype "bidirectional"))
      (node (ref "U4") (pin "27") (pinfunction "PD2(RXD1/INT2)_27") (pintype "bidirectional"))
    )
    (net (code "19") (name "FTDI3V3") (class "Default")
      (node (ref "C9") (pin "1") (pinfunction "1_1") (pintype "passive"))
      (node (ref "U3") (pin "17") (pinfunction "3V3OUT_17") (pintype "output"))
      (node (ref "U3") (pin "4") (pinfunction "VCCIO_4") (pintype "power_in"))
    )
    (net (code "20") (name "GND") (class "Default")
      (node (ref "B1") (pin "3") (pinfunction "2_3") (pintype "passive"))
      (node (ref "B1") (pin "4") (pinfunction "2_4") (pintype "passive"))
      (node (ref "B10") (pin "3") (pinfunction "2_3") (pintype "passive"))
      (node (ref "B10") (pin "4") (pinfunction "2_4") (pintype "passive"))
      (node (ref "B2") (pin "5") (pinfunction "GND_5") (pintype "bidirectional"))
      (node (ref "B3") (pin "2") (pinfunction "2_2") (pintype "passive"))
      (node (ref "B4") (pin "1") (pinfunction "1_1") (pintype "passive"))
      (node (ref "B4") (pin "2") (pinfunction "1_2") (pintype "passive"))
      (node (ref "B5") (pin "1") (pinfunction "1_1") (pintype "passive"))
      (node (ref "B5") (pin "2") (pinfunction "1_2") (pintype "passive"))
      (node (ref "B6") (pin "3") (pinfunction "2_3") (pintype "passive"))
      (node (ref "B6") (pin "4") (pinfunction "2_4") (pintype "passive"))
      (node (ref "B7") (pin "3") (pinfunction "2_3") (pintype "passive"))
      (node (ref "B7") (pin "4") (pinfunction "2_4") (pintype "passive"))
      (node (ref "B8") (pin "3") (pinfunction "2_3") (pintype "passive"))
      (node (ref "B8") (pin "4") (pinfunction "2_4") (pintype "passive"))
      (node (ref "B9") (pin "3") (pinfunction "2_3") (pintype "passive"))
      (node (ref "B9") (pin "4") (pinfunction "2_4") (pintype "passive"))
      (node (ref "C11") (pin "2") (pinfunction "2_2") (pintype "passive"))
      (node (ref "C12") (pin "2") (pinfunction "2_2") (pintype "passive"))
      (node (ref "C13") (pin "2") (pinfunction "2_2") (pintype "passive"))
      (node (ref "C14") (pin "2") (pinfunction "2_2") (pintype "passive"))
      (node (ref "C15") (pin "2") (pinfunction "2_2") (pintype "passive"))
      (node (ref "C16") (pin "2") (pinfunction "2_2") (pintype "passive"))
      (node (ref "C18") (pin "2") (pinfunction "2_2") (pintype "passive"))
      (node (ref "C19") (pin "2") (pinfunction "2_2") (pintype "passive"))
      (node (ref "C2") (pin "2") (pinfunction "2_2") (pintype "passive"))
      (node (ref "C20") (pin "2") (pinfunction "2_2") (pintype "passive"))
      (node (ref "C23") (pin "2") (pinfunction "2_2") (pintype "passive"))
      (node (ref "C26") (pin "2") (pinfunction "2_2") (pintype "passive"))
      (node (ref "C3") (pin "1") (pinfunction "1_1") (pintype "passive"))
      (node (ref "C4") (pin "1") (pinfunction "1_1") (pintype "passive"))
      (node (ref "C5") (pin "2") (pinfunction "2_2") (pintype "passive"))
      (node (ref "C6") (pin "2") (pinfunction "2_2") (pintype "passive"))
      (node (ref "C7") (pin "2") (pinfunction "2_2") (pintype "passive"))
      (node (ref "C8") (pin "2") (pinfunction "2_2") (pintype "passive"))
      (node (ref "C9") (pin "2") (pinfunction "2_2") (pintype "passive"))
      (node (ref "D1") (pin "C1") (pinfunction "C1_C1") (pintype "passive"))
      (node (ref "E1") (pin "BUTB") (pinfunction "X_BUTB") (pintype "bidirectional"))
      (node (ref "E1") (pin "C") (pinfunction "C_C") (pintype "bidirectional"))
      (node (ref "H1") (pin "1") (pinfunction "P_1") (pintype "bidirectional"))
      (node (ref "H1") (pin "2") (pinfunction "P_2") (pintype "bidirectional"))
      (node (ref "H1") (pin "3") (pinfunction "P_3") (pintype "bidirectional"))
      (node (ref "H1") (pin "4") (pinfunction "P_4") (pintype "bidirectional"))
      (node (ref "H1") (pin "5") (pinfunction "P_5") (pintype "bidirectional"))
      (node (ref "H1") (pin "6") (pinfunction "P_6") (pintype "bidirectional"))
      (node (ref "H1") (pin "7") (pinfunction "P_7") (pintype "bidirectional"))
      (node (ref "H1") (pin "8") (pinfunction "P_8") (pintype "bidirectional"))
      (node (ref "H2") (pin "1") (pinfunction "P_1") (pintype "bidirectional"))
      (node (ref "H2") (pin "2") (pinfunction "P_2") (pintype "bidirectional"))
      (node (ref "H2") (pin "3") (pinfunction "P_3") (pintype "bidirectional"))
      (node (ref "H2") (pin "4") (pinfunction "P_4") (pintype "bidirectional"))
      (node (ref "H2") (pin "5") (pinfunction "P_5") (pintype "bidirectional"))
      (node (ref "H2") (pin "6") (pinfunction "P_6") (pintype "bidirectional"))
      (node (ref "H2") (pin "7") (pinfunction "P_7") (pintype "bidirectional"))
      (node (ref "H2") (pin "8") (pinfunction "P_8") (pintype "bidirectional"))
      (node (ref "H3") (pin "1") (pinfunction "P_1") (pintype "bidirectional"))
      (node (ref "H3") (pin "2") (pinfunction "P_2") (pintype "bidirectional"))
      (node (ref "H3") (pin "3") (pinfunction "P_3") (pintype "bidirectional"))
      (node (ref "H3") (pin "4") (pinfunction "P_4") (pintype "bidirectional"))
      (node (ref "H3") (pin "5") (pinfunction "P_5") (pintype "bidirectional"))
      (node (ref "H3") (pin "6") (pinfunction "P_6") (pintype "bidirectional"))
      (node (ref "H3") (pin "7") (pinfunction "P_7") (pintype "bidirectional"))
      (node (ref "H3") (pin "8") (pinfunction "P_8") (pintype "bidirectional"))
      (node (ref "H4") (pin "1") (pinfunction "P_1") (pintype "bidirectional"))
      (node (ref "H4") (pin "2") (pinfunction "P_2") (pintype "bidirectional"))
      (node (ref "H4") (pin "3") (pinfunction "P_3") (pintype "bidirectional"))
      (node (ref "H4") (pin "4") (pinfunction "P_4") (pintype "bidirectional"))
      (node (ref "H4") (pin "5") (pinfunction "P_5") (pintype "bidirectional"))
      (node (ref "H4") (pin "6") (pinfunction "P_6") (pintype "bidirectional"))
      (node (ref "H4") (pin "7") (pinfunction "P_7") (pintype "bidirectional"))
      (node (ref "H4") (pin "8") (pinfunction "P_8") (pintype "bidirectional"))
      (node (ref "J1") (pin "10") (pinfunction "5-GND_10") (pintype "bidirectional"))
      (node (ref "J1") (pin "11") (pinfunction "5-GND_11") (pintype "bidirectional"))
      (node (ref "J1") (pin "5") (pinfunction "5-GND_5") (pintype "bidirectional"))
      (node (ref "J1") (pin "6") (pinfunction "5-GND_6") (pintype "bidirectional"))
      (node (ref "J1") (pin "7") (pinfunction "5-GND_7") (pintype "bidirectional"))
      (node (ref "J1") (pin "8") (pinfunction "5-GND_8") (pintype "bidirectional"))
      (node (ref "J1") (pin "9") (pinfunction "5-GND_9") (pintype "bidirectional"))
      (node (ref "J2") (pin "3") (pinfunction "-_3") (pintype "bidirectional"))
      (node (ref "J2") (pin "6") (pinfunction "-_6") (pintype "bidirectional"))
      (node (ref "J3") (pin "3") (pinfunction "-_3") (pintype "bidirectional"))
      (node (ref "J3") (pin "6") (pinfunction "-_6") (pintype "bidirectional"))
      (node (ref "J4") (pin "6") (pinfunction "6_6") (pintype "passive"))
      (node (ref "J6") (pin "1") (pinfunction "1_1") (pintype "passive"))
      (node (ref "J7") (pin "3") (pinfunction "-_3") (pintype "bidirectional"))
      (node (ref "J7") (pin "6") (pinfunction "-_6") (pintype "bidirectional"))
      (node (ref "J8") (pin "3") (pinfunction "-_3") (pintype "bidirectional"))
      (node (ref "J8") (pin "6") (pinfunction "-_6") (pintype "bidirectional"))
      (node (ref "L1") (pin "GND2") (pinfunction "GND_GND2") (pintype "bidirectional"))
      (node (ref "P4") (pin "T") (pinfunction "T_T") (pintype "bidirectional"))
      (node (ref "R15") (pin "1") (pinfunction "1_1") (pintype "passive"))
      (node (ref "R16") (pin "1") (pinfunction "1_1") (pintype "passive"))
      (node (ref "R17") (pin "1") (pinfunction "1_1") (pintype "passive"))
      (node (ref "R18") (pin "1") (pinfunction "1_1") (pintype "passive"))
      (node (ref "R4") (pin "1") (pinfunction "1_1") (pintype "passive"))
      (node (ref "R7") (pin "2") (pinfunction "2_2") (pintype "passive"))
      (node (ref "S2") (pin "A") (pinfunction "OFF_A") (pintype "bidirectional"))
      (node (ref "U1") (pin "2") (pinfunction "GND_2") (pintype "input"))
      (node (ref "U2") (pin "2") (pinfunction "VSS_2") (pintype "power_in"))
      (node (ref "U3") (pin "18") (pinfunction "GND18_18") (pintype "power_in"))
      (node (ref "U3") (pin "21") (pinfunction "GND21_21") (pintype "power_in"))
      (node (ref "U3") (pin "25") (pinfunction "AGND_25") (pintype "power_in"))
      (node (ref "U3") (pin "26") (pinfunction "TEST_26") (pintype "input"))
      (node (ref "U3") (pin "7") (pinfunction "GND7_7") (pintype "power_in"))
      (node (ref "U4") (pin "10") (pinfunction "AVSS_RFN_10") (pintype "bidirectional"))
      (node (ref "U4") (pin "11") (pinfunction "TST_11") (pintype "bidirectional"))
      (node (ref "U4") (pin "20") (pinfunction "DVSS_20") (pintype "bidirectional"))
      (node (ref "U4") (pin "24") (pinfunction "DVSS_24") (pintype "bidirectional"))
      (node (ref "U4") (pin "33") (pinfunction "CLKI_33") (pintype "bidirectional"))
      (node (ref "U4") (pin "35") (pinfunction "DVSS_35") (pintype "bidirectional"))
      (node (ref "U4") (pin "45") (pinfunction "DVSS_45") (pintype "bidirectional"))
      (node (ref "U4") (pin "55") (pinfunction "DVSS_55") (pintype "bidirectional"))
      (node (ref "U4") (pin "58") (pinfunction "AVSS_58") (pintype "bidirectional"))
      (node (ref "U4") (pin "61") (pinfunction "AVSS_61") (pintype "bidirectional"))
      (node (ref "U4") (pin "7") (pinfunction "AVSS_RFP_7") (pintype "bidirectional"))
      (node (ref "U5") (pin "8") (pinfunction "GND_8") (pintype "bidirectional"))
      (node (ref "U6") (pin "GND1") (pinfunction "GND_GND1") (pintype "bidirectional"))
      (node (ref "U6") (pin "GND2") (pinfunction "GND_GND2") (pintype "bidirectional"))
      (node (ref "U6") (pin "RES1") (pinfunction "RES_RES1") (pintype "bidirectional"))
      (node (ref "U6") (pin "RES2") (pinfunction "RES_RES2") (pintype "bidirectional"))
      (node (ref "U6") (pin "RES3") (pinfunction "RES_RES3") (pintype "bidirectional"))
      (node (ref "U6") (pin "RES4") (pinfunction "RES_RES4") (pintype "bidirectional"))
      (node (ref "U6") (pin "RES5") (pinfunction "RES_RES5") (pintype "bidirectional"))
      (node (ref "V3") (pin "P1") (pinfunction "N_P1") (pintype "bidirectional"))
      (node (ref "V35") (pin "P1") (pinfunction "N_P1") (pintype "bidirectional"))
      (node (ref "V37") (pin "P1") (pinfunction "N_P1") (pintype "bidirectional"))
      (node (ref "V38") (pin "P1") (pinfunction "N_P1") (pintype "bidirectional"))
      (node (ref "V4") (pin "P1") (pinfunction "N_P1") (pintype "bidirectional"))
      (node (ref "V5") (pin "P1") (pinfunction "N_P1") (pintype "bidirectional"))
      (node (ref "V7") (pin "P1") (pinfunction "N_P1") (pintype "bidirectional"))
      (node (ref "V8") (pin "P1") (pinfunction "N_P1") (pintype "bidirectional"))
    )
    (net (code "21") (name "GREF") (class "Default")
      (node (ref "J2") (pin "1") (pinfunction "+_1") (pintype "bidirectional"))
      (node (ref "J2") (pin "4") (pinfunction "+_4") (pintype "bidirectional"))
      (node (ref "J3") (pin "1") (pinfunction "+_1") (pintype "bidirectional"))
      (node (ref "J3") (pin "4") (pinfunction "+_4") (pintype "bidirectional"))
      (node (ref "J7") (pin "1") (pinfunction "+_1") (pintype "bidirectional"))
      (node (ref "J7") (pin "4") (pinfunction "+_4") (pintype "bidirectional"))
      (node (ref "J8") (pin "1") (pinfunction "+_1") (pintype "bidirectional"))
      (node (ref "J8") (pin "4") (pinfunction "+_4") (pintype "bidirectional"))
      (node (ref "R8") (pin "1") (pinfunction "1_1") (pintype "passive"))
    )
    (net (code "22") (name "LCD_RX") (class "Default")
      (node (ref "L1") (pin "RX1") (pinfunction "RX_RX1") (pintype "bidirectional"))
      (node (ref "U4") (pin "32") (pinfunction "PD7(T0)_32") (pintype "bidirectional"))
    )
    (net (code "23") (name "LCD_TX") (class "Default")
      (node (ref "L1") (pin "TX0") (pinfunction "TX_TX0") (pintype "bidirectional"))
      (node (ref "U4") (pin "31") (pinfunction "PD6(T1)_31") (pintype "bidirectional"))
    )
    (net (code "24") (name "MISO") (class "Default")
      (node (ref "J4") (pin "1") (pinfunction "1_1") (pintype "passive"))
      (node (ref "U4") (pin "39") (pinfunction "PB3(MISO/PDO/PCINT3)_39") (pintype "bidirectional"))
    )
    (net (code "25") (name "MOSI") (class "Default")
      (node (ref "J4") (pin "4") (pinfunction "4_4") (pintype "passive"))
      (node (ref "U4") (pin "38") (pinfunction "PB2(MOSI/PDI/PCINT2)_38") (pintype "bidirectional"))
    )
    (net (code "26") (name "Net-(A1-SIGNAL)") (class "Default")
      (node (ref "A1") (pin "FEED") (pinfunction "SIGNAL_FEED") (pintype "bidirectional"))
      (node (ref "B2") (pin "1") (pinfunction "IN_1") (pintype "bidirectional"))
      (node (ref "C2") (pin "1") (pinfunction "1_1") (pintype "passive"))
    )
    (net (code "27") (name "Net-(B2-GND-Pad2)") (class "Default")
      (node (ref "B2") (pin "2") (pinfunction "GND_2") (pintype "bidirectional"))
      (node (ref "C3") (pin "2") (pinfunction "2_2") (pintype "passive"))
    )
    (net (code "28") (name "Net-(B2-OUT1)") (class "Default")
      (node (ref "B2") (pin "4") (pinfunction "OUT1_4") (pintype "bidirectional"))
      (node (ref "U4") (pin "8") (pinfunction "RFP_8") (pintype "bidirectional"))
    )
    (net (code "29") (name "Net-(B2-OUT2)") (class "Default")
      (node (ref "B2") (pin "3") (pinfunction "OUT2_3") (pintype "bidirectional"))
      (node (ref "U4") (pin "9") (pinfunction "RFN_9") (pintype "bidirectional"))
    )
    (net (code "30") (name "Net-(C11-Pad1)") (class "Default")
      (node (ref "C11") (pin "1") (pinfunction "1_1") (pintype "passive"))
      (node (ref "U4") (pin "21") (pinfunction "DVDD_21") (pintype "bidirectional"))
      (node (ref "U4") (pin "22") (pinfunction "DVDD_22") (pintype "bidirectional"))
    )
    (net (code "31") (name "Net-(C18-Pad1)") (class "Default")
      (node (ref "C18") (pin "1") (pinfunction "1_1") (pintype "passive"))
      (node (ref "U6") (pin "CAP") (pinfunction "CAP_CAP") (pintype "bidirectional"))
    )
    (net (code "32") (name "Net-(C19-Pad1)") (class "Default")
      (node (ref "C19") (pin "1") (pinfunction "1_1") (pintype "passive"))
      (node (ref "U6") (pin "C1") (pinfunction "C1_C1") (pintype "bidirectional"))
    )
    (net (code "33") (name "Net-(D1-PadA1)") (class "Default")
      (node (ref "D1") (pin "A1") (pinfunction "A1_A1") (pintype "passive"))
      (node (ref "R3") (pin "1") (pinfunction "1_1") (pintype "passive"))
    )
    (net (code "34") (name "Net-(D1-PadC2)") (class "Default")
      (node (ref "D1") (pin "C2") (pinfunction "C2_C2") (pintype "passive"))
      (node (ref "R1") (pin "1") (pinfunction "1_1") (pintype "passive"))
    )
    (net (code "35") (name "Net-(D4-PadC1)") (class "Default")
      (node (ref "D4") (pin "C1") (pinfunction "C1_C1") (pintype "passive"))
      (node (ref "R15") (pin "2") (pinfunction "2_2") (pintype "passive"))
    )
    (net (code "36") (name "Net-(D4-PadC2)") (class "Default")
      (node (ref "D4") (pin "C2") (pinfunction "C2_C2") (pintype "passive"))
      (node (ref "R16") (pin "2") (pinfunction "2_2") (pintype "passive"))
    )
    (net (code "37") (name "Net-(D5-PadA1)") (class "Default")
      (node (ref "D5") (pin "A1") (pinfunction "A1_A1") (pintype "passive"))
      (node (ref "R14") (pin "1") (pinfunction "1_1") (pintype "passive"))
    )
    (net (code "38") (name "Net-(D5-PadA2)") (class "Default")
      (node (ref "D5") (pin "A2") (pinfunction "A2_A2") (pintype "passive"))
      (node (ref "R13") (pin "1") (pinfunction "1_1") (pintype "passive"))
    )
    (net (code "39") (name "Net-(D6-PadC1)") (class "Default")
      (node (ref "D6") (pin "C1") (pinfunction "C1_C1") (pintype "passive"))
      (node (ref "R18") (pin "2") (pinfunction "2_2") (pintype "passive"))
    )
    (net (code "40") (name "Net-(D6-PadC2)") (class "Default")
      (node (ref "D6") (pin "C2") (pinfunction "C2_C2") (pintype "passive"))
      (node (ref "R17") (pin "2") (pinfunction "2_2") (pintype "passive"))
    )
    (net (code "41") (name "Net-(J5-Pad2)") (class "Default")
      (node (ref "J5") (pin "2") (pinfunction "2_2") (pintype "passive"))
      (node (ref "J6") (pin "3") (pinfunction "3_3") (pintype "passive"))
    )
    (net (code "42") (name "Net-(S1-ON)") (class "Default")
      (node (ref "J9") (pin "2") (pinfunction "2_2") (pintype "passive"))
      (node (ref "S1") (pin "B") (pinfunction "ON_B") (pintype "bidirectional"))
      (node (ref "U1") (pin "3") (pinfunction "EN_3") (pintype "input"))
    )
    (net (code "43") (name "Net-(U2-PROG)") (class "Default")
      (node (ref "R7") (pin "1") (pinfunction "1_1") (pintype "passive"))
      (node (ref "U2") (pin "5") (pinfunction "PROG_5") (pintype "input"))
    )
    (net (code "44") (name "Net-(U2-STAT)") (class "Default")
      (node (ref "R1") (pin "2") (pinfunction "2_2") (pintype "passive"))
      (node (ref "R3") (pin "2") (pinfunction "2_2") (pintype "passive"))
      (node (ref "U2") (pin "1") (pinfunction "STAT_1") (pintype "output"))
    )
    (net (code "45") (name "Net-(U2-VBAT)") (class "Default")
      (node (ref "B3") (pin "1") (pinfunction "1_1") (pintype "passive"))
      (node (ref "C6") (pin "1") (pinfunction "1_1") (pintype "passive"))
      (node (ref "D3") (pin "A") (pinfunction "A_A") (pintype "passive"))
      (node (ref "R5") (pin "2") (pinfunction "2_2") (pintype "passive"))
      (node (ref "U2") (pin "3") (pinfunction "VBAT_3") (pintype "power_in"))
      (node (ref "V30") (pin "P1") (pinfunction "N_P1") (pintype "bidirectional"))
      (node (ref "V31") (pin "P1") (pinfunction "N_P1") (pintype "bidirectional"))
      (node (ref "V32") (pin "P1") (pinfunction "N_P1") (pintype "bidirectional"))
      (node (ref "V33") (pin "P1") (pinfunction "N_P1") (pintype "bidirectional"))
      (node (ref "V34") (pin "P1") (pinfunction "N_P1") (pintype "bidirectional"))
      (node (ref "V36") (pin "P1") (pinfunction "N_P1") (pintype "bidirectional"))
      (node (ref "V6") (pin "P1") (pinfunction "N_P1") (pintype "bidirectional"))
    )
    (net (code "46") (name "Net-(U4-AVDD)") (class "Default")
      (node (ref "C13") (pin "1") (pinfunction "1_1") (pintype "passive"))
      (node (ref "U4") (pin "60") (pinfunction "AVDD_60") (pintype "bidirectional"))
    )
    (net (code "47") (name "Net-(U4-PG0(DIG3))") (class "Default")
      (node (ref "D6") (pin "A2") (pinfunction "A2_A2") (pintype "passive"))
      (node (ref "U4") (pin "14") (pinfunction "PG0(DIG3)_14") (pintype "bidirectional"))
    )
    (net (code "48") (name "Net-(U4-PG1(DIG1))") (class "Default")
      (node (ref "D6") (pin "A1") (pinfunction "A1_A1") (pintype "passive"))
      (node (ref "U4") (pin "15") (pinfunction "PG1(DIG1)_15") (pintype "bidirectional"))
    )
    (net (code "49") (name "Net-(U4-XTAL1)") (class "Default")
      (node (ref "C14") (pin "1") (pinfunction "1_1") (pintype "passive"))
      (node (ref "U4") (pin "57") (pinfunction "XTAL1_57") (pintype "bidirectional"))
      (node (ref "Y1") (pin "3") (pinfunction "2_3") (pintype "passive"))
    )
    (net (code "50") (name "Net-(U4-XTAL2)") (class "Default")
      (node (ref "C15") (pin "1") (pinfunction "1_1") (pintype "passive"))
      (node (ref "U4") (pin "56") (pinfunction "XTAL2_56") (pintype "bidirectional"))
      (node (ref "Y1") (pin "1") (pinfunction "1_1") (pintype "passive"))
    )
    (net (code "51") (name "Net-(U5-1S)") (class "Default")
      (node (ref "S2") (pin "C") (pinfunction "C_C") (pintype "bidirectional"))
      (node (ref "U5") (pin "12") (pinfunction "2S_12") (pintype "bidirectional"))
      (node (ref "U5") (pin "4") (pinfunction "1S_4") (pintype "bidirectional"))
    )
    (net (code "52") (name "PITCH") (class "Default")
      (node (ref "J3") (pin "V") (pinfunction "V_V") (pintype "bidirectional"))
      (node (ref "J8") (pin "V") (pinfunction "V_V") (pintype "bidirectional"))
      (node (ref "U4") (pin "2") (pinfunction "PF3(ADC3/DIG4)_2") (pintype "bidirectional"))
    )
    (net (code "53") (name "RESET") (class "Default")
      (node (ref "B1") (pin "1") (pinfunction "1_1") (pintype "passive"))
      (node (ref "B1") (pin "2") (pinfunction "1_2") (pintype "passive"))
      (node (ref "C1") (pin "1") (pinfunction "1_1") (pintype "passive"))
      (node (ref "J4") (pin "5") (pinfunction "5_5") (pintype "passive"))
      (node (ref "R2") (pin "1") (pinfunction "1_1") (pintype "passive"))
      (node (ref "U4") (pin "12") (pinfunction "RSTN_12") (pintype "bidirectional"))
    )
    (net (code "54") (name "RF") (class "Default")
      (node (ref "D4") (pin "A1") (pinfunction "A1_A1") (pintype "passive"))
      (node (ref "U4") (pin "16") (pinfunction "PG2(AMR)_16") (pintype "bidirectional"))
    )
    (net (code "55") (name "ROLL") (class "Default")
      (node (ref "J3") (pin "H") (pinfunction "H_H") (pintype "bidirectional"))
      (node (ref "J8") (pin "H") (pinfunction "H_H") (pintype "bidirectional"))
      (node (ref "U4") (pin "1") (pinfunction "PF2(ADC2/DIG2)_1") (pintype "bidirectional"))
    )
    (net (code "56") (name "RXI") (class "Default")
      (node (ref "U3") (pin "5") (pinfunction "RXD_5") (pintype "input"))
      (node (ref "U5") (pin "10") (pinfunction "3Z_10") (pintype "bidirectional"))
    )
    (net (code "57") (name "RXI-0") (class "Default")
      (node (ref "J10") (pin "2") (pinfunction "2_2") (pintype "passive"))
      (node (ref "U4") (pin "47") (pinfunction "PE1(TXD0)_47") (pintype "bidirectional"))
      (node (ref "U5") (pin "11") (pinfunction "3Y0_11") (pintype "bidirectional"))
    )
    (net (code "58") (name "RXI-1") (class "Default")
      (node (ref "J10") (pin "1") (pinfunction "1_1") (pintype "passive"))
      (node (ref "J6") (pin "5") (pinfunction "5_5") (pintype "passive"))
      (node (ref "U5") (pin "9") (pinfunction "3Y1_9") (pintype "bidirectional"))
    )
    (net (code "59") (name "RXLED") (class "Default")
      (node (ref "D5") (pin "C2") (pinfunction "C2_C2") (pintype "passive"))
      (node (ref "U3") (pin "22") (pinfunction "RXLED_22") (pintype "input"))
    )
    (net (code "60") (name "SCK") (class "Default")
      (node (ref "J4") (pin "3") (pinfunction "3_3") (pintype "passive"))
      (node (ref "U4") (pin "37") (pinfunction "PB1(SCK/PCINT1)_37") (pintype "bidirectional"))
    )
    (net (code "61") (name "THROTTLE") (class "Default")
      (node (ref "J2") (pin "V") (pinfunction "V_V") (pintype "bidirectional"))
      (node (ref "J7") (pin "V") (pinfunction "V_V") (pintype "bidirectional"))
      (node (ref "U4") (pin "64") (pinfunction "PF1(ADC1)_64") (pintype "bidirectional"))
    )
    (net (code "62") (name "TXLED") (class "Default")
      (node (ref "D5") (pin "C1") (pinfunction "C1_C1") (pintype "passive"))
      (node (ref "U3") (pin "23") (pinfunction "TXLED_23") (pintype "input"))
    )
    (net (code "63") (name "TXO") (class "Default")
      (node (ref "U3") (pin "1") (pinfunction "TXD_1") (pintype "output"))
      (node (ref "U5") (pin "6") (pinfunction "2Z_6") (pintype "bidirectional"))
    )
    (net (code "64") (name "TXO-0") (class "Default")
      (node (ref "J11") (pin "2") (pinfunction "2_2") (pintype "passive"))
      (node (ref "U4") (pin "46") (pinfunction "PE0(RXD0/PCINT8)_46") (pintype "bidirectional"))
      (node (ref "U5") (pin "7") (pinfunction "2Y0_7") (pintype "bidirectional"))
    )
    (net (code "65") (name "TXO-1") (class "Default")
      (node (ref "J11") (pin "1") (pinfunction "1_1") (pintype "passive"))
      (node (ref "J6") (pin "4") (pinfunction "4_4") (pintype "passive"))
      (node (ref "U5") (pin "5") (pinfunction "2Y1_5") (pintype "bidirectional"))
    )
    (net (code "66") (name "USB_D_N") (class "Default")
      (node (ref "J1") (pin "2") (pinfunction "2-D-_2") (pintype "bidirectional"))
      (node (ref "U3") (pin "16") (pinfunction "USBDM_16") (pintype "bidirectional"))
    )
    (net (code "67") (name "USB_D_P") (class "Default")
      (node (ref "J1") (pin "3") (pinfunction "3-D+_3") (pintype "bidirectional"))
      (node (ref "U3") (pin "15") (pinfunction "USBDP_15") (pintype "bidirectional"))
    )
    (net (code "68") (name "VBAT") (class "Default")
      (node (ref "C7") (pin "1") (pinfunction "1_1") (pintype "passive"))
      (node (ref "C8") (pin "1") (pinfunction "1_1") (pintype "passive"))
      (node (ref "D2") (pin "C") (pinfunction "C_C") (pintype "passive"))
      (node (ref "D3") (pin "C") (pinfunction "C_C") (pintype "passive"))
      (node (ref "J9") (pin "1") (pinfunction "1_1") (pintype "passive"))
      (node (ref "L1") (pin "RAW") (pinfunction "VIN_RAW") (pintype "bidirectional"))
      (node (ref "P2") (pin "T") (pinfunction "T_T") (pintype "bidirectional"))
      (node (ref "R13") (pin "2") (pinfunction "2_2") (pintype "passive"))
      (node (ref "R14") (pin "2") (pinfunction "2_2") (pintype "passive"))
      (node (ref "S1") (pin "C") (pinfunction "C_C") (pintype "bidirectional"))
      (node (ref "U1") (pin "1") (pinfunction "IN_1") (pintype "input"))
      (node (ref "U3") (pin "20") (pinfunction "VCC_20") (pintype "power_in"))
    )
    (net (code "69") (name "VBUS") (class "Default")
      (node (ref "C5") (pin "1") (pinfunction "1_1") (pintype "passive"))
      (node (ref "D1") (pin "A2") (pinfunction "A2_A2") (pintype "passive"))
      (node (ref "D2") (pin "A") (pinfunction "A_A") (pintype "passive"))
      (node (ref "J1") (pin "1") (pinfunction "1-VCC_1") (pintype "bidirectional"))
      (node (ref "J5") (pin "3") (pinfunction "3_3") (pintype "passive"))
      (node (ref "P1") (pin "T") (pinfunction "T_T") (pintype "bidirectional"))
      (node (ref "U2") (pin "4") (pinfunction "VDD_4") (pintype "power_in"))
      (node (ref "V1") (pin "P1") (pinfunction "N_P1") (pintype "bidirectional"))
      (node (ref "V2") (pin "P1") (pinfunction "N_P1") (pintype "bidirectional"))
      (node (ref "V23") (pin "P1") (pinfunction "N_P1") (pintype "bidirectional"))
      (node (ref "V24") (pin "P1") (pinfunction "N_P1") (pintype "bidirectional"))
      (node (ref "V26") (pin "P1") (pinfunction "N_P1") (pintype "bidirectional"))
      (node (ref "V27") (pin "P1") (pinfunction "N_P1") (pintype "bidirectional"))
      (node (ref "V28") (pin "P1") (pinfunction "N_P1") (pintype "bidirectional"))
    )
    (net (code "70") (name "YAW") (class "Default")
      (node (ref "J2") (pin "H") (pinfunction "H_H") (pintype "bidirectional"))
      (node (ref "J7") (pin "H") (pinfunction "H_H") (pintype "bidirectional"))
      (node (ref "U4") (pin "63") (pinfunction "PF0(ADC0)_63") (pintype "bidirectional"))
    )
    (net (code "71") (name "unconnected-(J1-4-ID-Pad4)") (class "Default")
      (node (ref "J1") (pin "4") (pinfunction "4-ID_4") (pintype "bidirectional"))
    )
    (net (code "72") (name "unconnected-(L1-PadSCK)") (class "Default")
      (node (ref "L1") (pin "SCK") (pinfunction "SCK_SCK") (pintype "bidirectional"))
    )
    (net (code "73") (name "unconnected-(L1-PadSDI)") (class "Default")
      (node (ref "L1") (pin "SDI") (pinfunction "SDI_SDI") (pintype "bidirectional"))
    )
    (net (code "74") (name "unconnected-(L1-PadSDO)") (class "Default")
      (node (ref "L1") (pin "SDO") (pinfunction "SDO_SDO") (pintype "bidirectional"))
    )
    (net (code "75") (name "unconnected-(L1-Pad{slash}CS)") (class "Default")
      (node (ref "L1") (pin "/CS") (pinfunction "/CS_/CS") (pintype "bidirectional"))
    )
    (net (code "76") (name "unconnected-(L1-SCL-PadCL)") (class "Default")
      (node (ref "L1") (pin "CL") (pinfunction "SCL_CL") (pintype "bidirectional"))
    )
    (net (code "77") (name "unconnected-(L1-SDA-PadDA)") (class "Default")
      (node (ref "L1") (pin "DA") (pinfunction "SDA_DA") (pintype "bidirectional"))
    )
    (net (code "78") (name "unconnected-(S1-OFF-PadA)") (class "Default")
      (node (ref "S1") (pin "A") (pinfunction "OFF_A") (pintype "bidirectional"))
    )
    (net (code "79") (name "unconnected-(U1-NC{slash}FB-Pad4)") (class "Default")
      (node (ref "U1") (pin "4") (pinfunction "NC/FB_4") (pintype "passive"))
    )
    (net (code "80") (name "unconnected-(U3-DCD-Pad10)") (class "Default")
      (node (ref "U3") (pin "10") (pinfunction "DCD_10") (pintype "input"))
    )
    (net (code "81") (name "unconnected-(U3-DSR-Pad9)") (class "Default")
      (node (ref "U3") (pin "9") (pinfunction "DSR_9") (pintype "input"))
    )
    (net (code "82") (name "unconnected-(U3-OSCI-Pad27)") (class "Default")
      (node (ref "U3") (pin "27") (pinfunction "OSCI_27") (pintype "input"))
    )
    (net (code "83") (name "unconnected-(U3-OSCO-Pad28)") (class "Default")
      (node (ref "U3") (pin "28") (pinfunction "OSCO_28") (pintype "output"))
    )
    (net (code "84") (name "unconnected-(U3-PWREN-Pad14)") (class "Default")
      (node (ref "U3") (pin "14") (pinfunction "PWREN_14") (pintype "input"))
    )
    (net (code "85") (name "unconnected-(U3-RESET-Pad19)") (class "Default")
      (node (ref "U3") (pin "19") (pinfunction "RESET_19") (pintype "input"))
    )
    (net (code "86") (name "unconnected-(U3-RI-Pad6)") (class "Default")
      (node (ref "U3") (pin "6") (pinfunction "RI_6") (pintype "input"))
    )
    (net (code "87") (name "unconnected-(U3-RTS-Pad3)") (class "Default")
      (node (ref "U3") (pin "3") (pinfunction "RTS_3") (pintype "output"))
    )
    (net (code "88") (name "unconnected-(U3-SLEEP-Pad12)") (class "Default")
      (node (ref "U3") (pin "12") (pinfunction "SLEEP_12") (pintype "input"))
    )
    (net (code "89") (name "unconnected-(U3-TXDEN-Pad13)") (class "Default")
      (node (ref "U3") (pin "13") (pinfunction "TXDEN_13") (pintype "input"))
    )
    (net (code "90") (name "unconnected-(U4-AREF-Pad62)") (class "Default")
      (node (ref "U4") (pin "62") (pinfunction "AREF_62") (pintype "bidirectional"))
    )
    (net (code "91") (name "unconnected-(U4-PB0(SSN{slash}PCINT0)-Pad36)") (class "Default")
      (node (ref "U4") (pin "36") (pinfunction "PB0(SSN/PCINT0)_36") (pintype "bidirectional"))
    )
    (net (code "92") (name "unconnected-(U4-PB6(OC1B{slash}PCINT6)-Pad42)") (class "Default")
      (node (ref "U4") (pin "42") (pinfunction "PB6(OC1B/PCINT6)_42") (pintype "bidirectional"))
    )
    (net (code "93") (name "unconnected-(U4-PB7(OC0A{slash}OC1C{slash}PCINT7)-Pad43)") (class "Default")
      (node (ref "U4") (pin "43") (pinfunction "PB7(OC0A/OC1C/PCINT7)_43") (pintype "bidirectional"))
    )
    (net (code "94") (name "unconnected-(U4-PD4(ICP1)-Pad29)") (class "Default")
      (node (ref "U4") (pin "29") (pinfunction "PD4(ICP1)_29") (pintype "bidirectional"))
    )
    (net (code "95") (name "unconnected-(U4-PD5(XCK1)-Pad30)") (class "Default")
      (node (ref "U4") (pin "30") (pinfunction "PD5(XCK1)_30") (pintype "bidirectional"))
    )
    (net (code "96") (name "unconnected-(U4-PE2(XCK0{slash}AIN0)-Pad48)") (class "Default")
      (node (ref "U4") (pin "48") (pinfunction "PE2(XCK0/AIN0)_48") (pintype "bidirectional"))
    )
    (net (code "97") (name "unconnected-(U4-PE3(OC3A{slash}AIN1)-Pad49)") (class "Default")
      (node (ref "U4") (pin "49") (pinfunction "PE3(OC3A/AIN1)_49") (pintype "bidirectional"))
    )
    (net (code "98") (name "unconnected-(U4-PF5(ADC5{slash}TMS)-Pad4)") (class "Default")
      (node (ref "U4") (pin "4") (pinfunction "PF5(ADC5/TMS)_4") (pintype "bidirectional"))
    )
    (net (code "99") (name "unconnected-(U4-PF6(ADC6{slash}TDO)-Pad5)") (class "Default")
      (node (ref "U4") (pin "5") (pinfunction "PF6(ADC6/TDO)_5") (pintype "bidirectional"))
    )
    (net (code "100") (name "unconnected-(U4-PF7(ADC7{slash}TDI)-Pad6)") (class "Default")
      (node (ref "U4") (pin "6") (pinfunction "PF7(ADC7/TDI)_6") (pintype "bidirectional"))
    )
    (net (code "101") (name "unconnected-(U4-PG3(TOSC2)-Pad17)") (class "Default")
      (node (ref "U4") (pin "17") (pinfunction "PG3(TOSC2)_17") (pintype "bidirectional"))
    )
    (net (code "102") (name "unconnected-(U4-PG4(TOSC1)-Pad18)") (class "Default")
      (node (ref "U4") (pin "18") (pinfunction "PG4(TOSC1)_18") (pintype "bidirectional"))
    )
    (net (code "103") (name "unconnected-(U4-PG5(OC0B)-Pad19)") (class "Default")
      (node (ref "U4") (pin "19") (pinfunction "PG5(OC0B)_19") (pintype "bidirectional"))
    )
    (net (code "104") (name "unconnected-(U4-RSTON-Pad13)") (class "Default")
      (node (ref "U4") (pin "13") (pinfunction "RSTON_13") (pintype "bidirectional"))
    )
    (net (code "105") (name "unconnected-(U6-PadDRDY_M)") (class "Default")
      (node (ref "U6") (pin "DRDY_M") (pinfunction "DRDY_M_DRDY_M") (pintype "bidirectional"))
    )
    (net (code "106") (name "unconnected-(U6-PadINT1_A{slash}G)") (class "Default")
      (node (ref "U6") (pin "INT1_A/G") (pinfunction "INT1_A/G_INT1_A/G") (pintype "bidirectional"))
    )
    (net (code "107") (name "unconnected-(U6-PadINT2_A{slash}G)") (class "Default")
      (node (ref "U6") (pin "INT2_A/G") (pinfunction "INT2_A/G_INT2_A/G") (pintype "bidirectional"))
    )
    (net (code "108") (name "unconnected-(U6-PadINT_M)") (class "Default")
      (node (ref "U6") (pin "INT_M") (pinfunction "INT_M_INT_M") (pintype "bidirectional"))
    )
  )
)
